# G824A.net
KiCad netlist of a schematic drawn in EAGLE
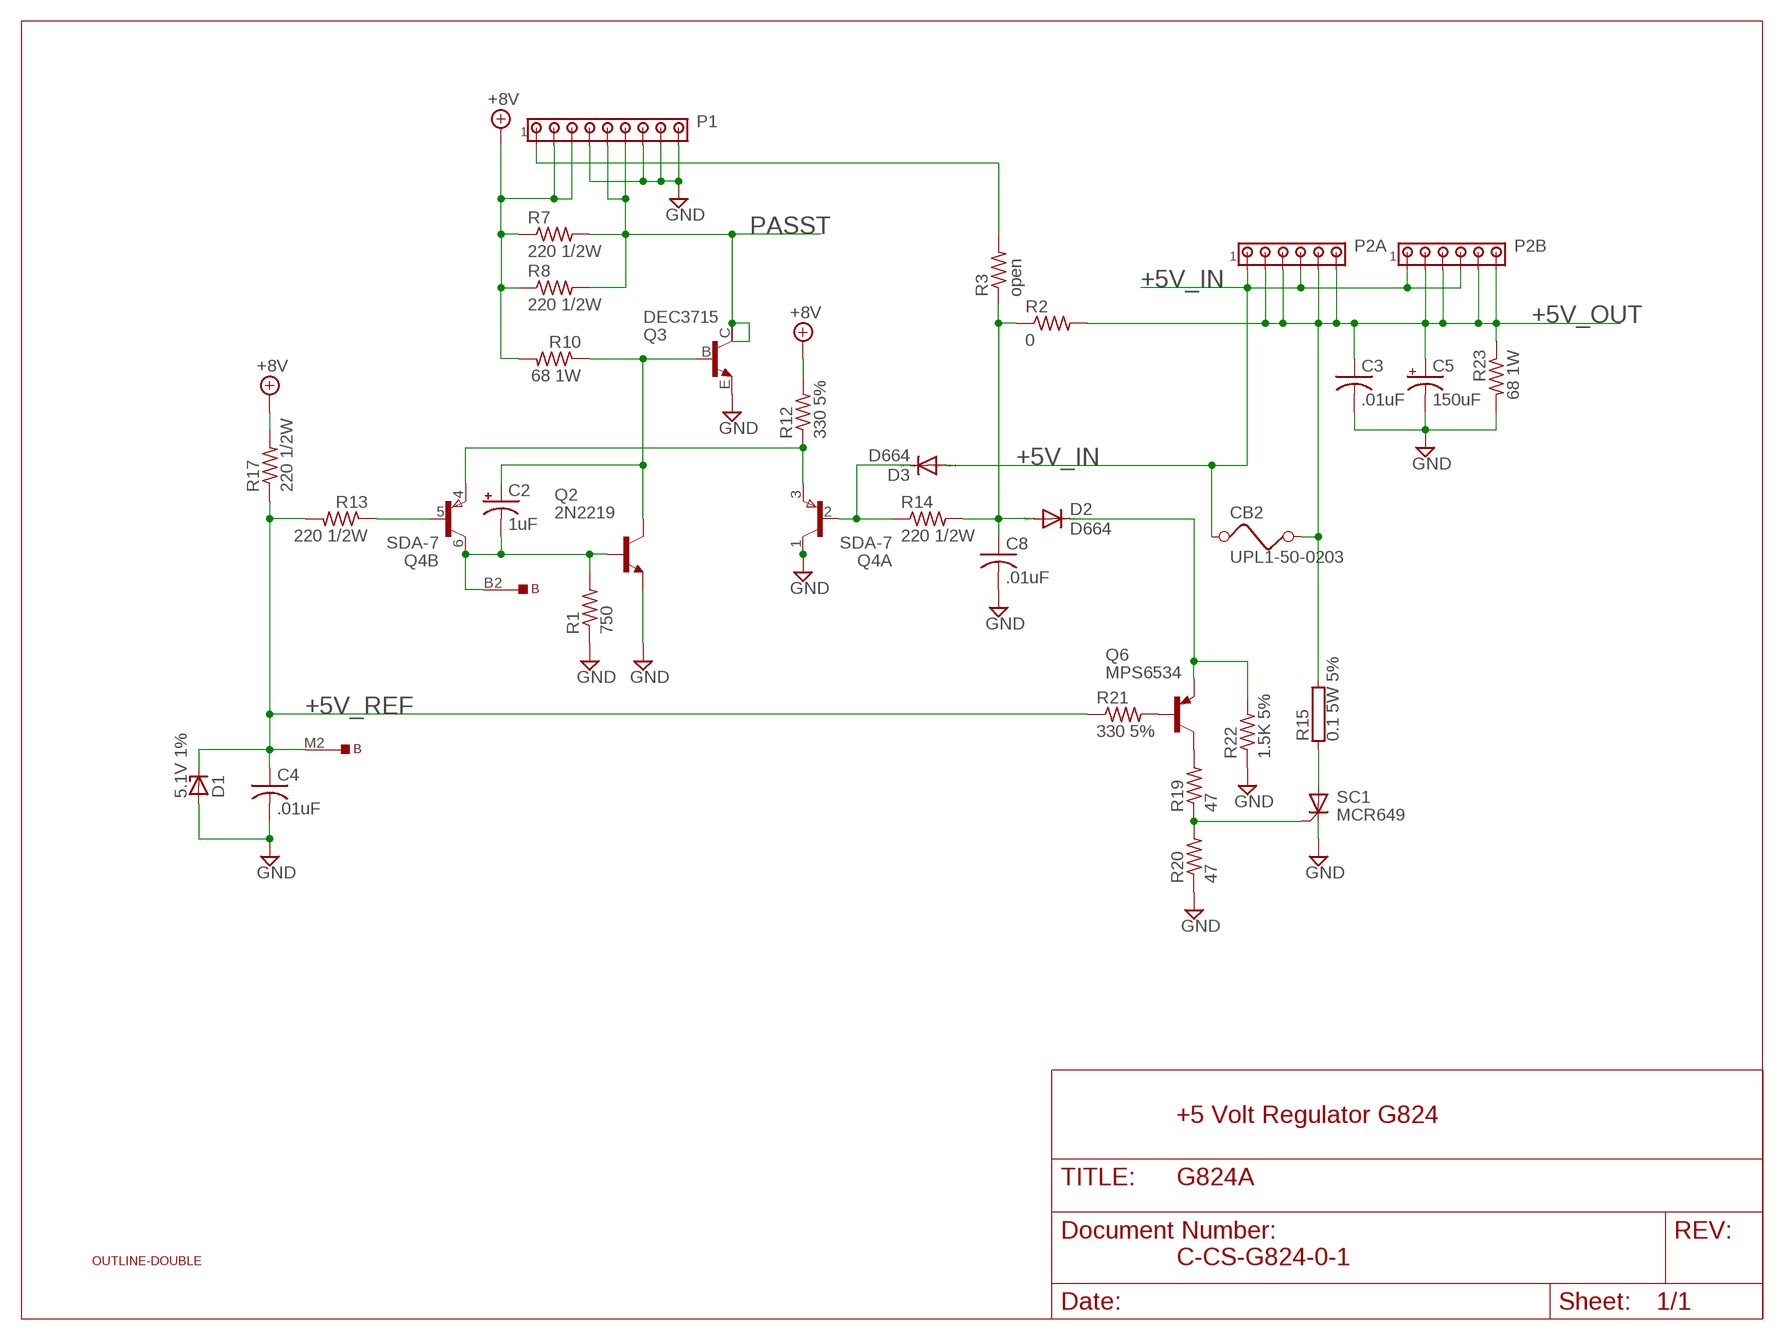
[diagram p0: schematic, sheet 1]

(export (version "E")
  (design (tool "Eeschema 10.0.6"))
  (components
    (comp (ref "B")
      (value "EDGE-TOP")
      (footprint "eagle-import:EDGE-CON2")
      (libsource (lib "eagle-import") (part "EDGE-TOP"))
    )
    (comp (ref "C2")
      (value "1uF")
      (footprint "eagle-import:E15-5")
      (libsource (lib "eagle-import") (part "CPOL-USE15-5AXIAL"))
    )
    (comp (ref "C3")
      (value ".01uF")
      (footprint "eagle-import:C063-025X075")
      (libsource (lib "eagle-import") (part "C-US"))
    )
    (comp (ref "C4")
      (value ".01uF")
      (footprint "eagle-import:C063-025X075")
      (libsource (lib "eagle-import") (part "C-US"))
    )
    (comp (ref "C5")
      (value "150uF")
      (footprint "eagle-import:E12-8")
      (libsource (lib "eagle-import") (part "CPOL-USE20-8AXIAL"))
    )
    (comp (ref "C8")
      (value ".01uF")
      (footprint "eagle-import:C063-025X075")
      (libsource (lib "eagle-import") (part "C-US"))
    )
    (comp (ref "CB2")
      (value "UPL1-50-0203")
      (footprint "eagle-import:UPL1-50")
      (libsource (lib "eagle-import") (part "UPL1-50"))
    )
    (comp (ref "D1")
      (value "5.1V 1%")
      (footprint "eagle-import:DO41Z10")
      (libsource (lib "eagle-import") (part "ZENER-DIODEDO41Z10"))
    )
    (comp (ref "D2")
      (value "D664")
      (footprint "eagle-import:DO35-10")
      (libsource (lib "eagle-import") (part "DIODE-DO35-10"))
    )
    (comp (ref "D3")
      (value "D664")
      (footprint "eagle-import:DO35-10")
      (libsource (lib "eagle-import") (part "DIODE-DO35-10"))
    )
    (comp (ref "P1")
      (value "350432-1")
      (footprint "eagle-import:350432-1")
      (libsource (lib "eagle-import") (part "350432-1"))
    )
    (comp (ref "P2A")
      (value "350431-1")
      (footprint "eagle-import:350431-1")
      (libsource (lib "eagle-import") (part "350431-1"))
    )
    (comp (ref "P2B")
      (value "350431-1")
      (footprint "eagle-import:350431-1")
      (libsource (lib "eagle-import") (part "350431-1"))
    )
    (comp (ref "Q2")
      (value "2N2219")
      (footprint "eagle-import:TO5")
      (libsource (lib "eagle-import") (part "2N2219"))
    )
    (comp (ref "Q3")
      (value "DEC3715")
      (footprint "eagle-import:TO3")
      (libsource (lib "eagle-import") (part "2N3772"))
    )
    (comp (ref "Q4")
      (value "SDA-7")
      (footprint "eagle-import:TO78")
      (libsource (lib "eagle-import") (part "MAT-03H"))
    )
    (comp (ref "Q6")
      (value "MPS6534")
      (footprint "eagle-import:TO5")
      (libsource (lib "eagle-import") (part "-PNP-TO5"))
    )
    (comp (ref "R1")
      (value "750")
      (footprint "eagle-import:0207_10")
      (libsource (lib "eagle-import") (part "R-US_0207/10"))
    )
    (comp (ref "R2")
      (value "0")
      (footprint "eagle-import:0207_10")
      (libsource (lib "eagle-import") (part "R-US_0207/10"))
    )
    (comp (ref "R3")
      (value "open")
      (footprint "eagle-import:0207_10")
      (libsource (lib "eagle-import") (part "R-US_0207/10"))
    )
    (comp (ref "R7")
      (value "220 1/2W")
      (footprint "eagle-import:0411_15")
      (libsource (lib "eagle-import") (part "R-US_0411/15"))
    )
    (comp (ref "R8")
      (value "220 1/2W")
      (footprint "eagle-import:0411_15")
      (libsource (lib "eagle-import") (part "R-US_0411/15"))
    )
    (comp (ref "R10")
      (value "68 1W")
      (footprint "eagle-import:0414_20")
      (libsource (lib "eagle-import") (part "R-US_0414/20"))
    )
    (comp (ref "R12")
      (value "330 5%")
      (footprint "eagle-import:0207_10")
      (libsource (lib "eagle-import") (part "R-US_0207/10"))
    )
    (comp (ref "R13")
      (value "220 1/2W")
      (footprint "eagle-import:0411_15")
      (libsource (lib "eagle-import") (part "R-US_0411/15"))
    )
    (comp (ref "R14")
      (value "220 1/2W")
      (footprint "eagle-import:0411_15")
      (libsource (lib "eagle-import") (part "R-US_0411/15"))
    )
    (comp (ref "R15")
      (value "0.1 5W 5%")
      (footprint "eagle-import:HPS932")
      (libsource (lib "eagle-import") (part "RHPS932"))
    )
    (comp (ref "R17")
      (value "220 1/2W")
      (footprint "eagle-import:0411_15")
      (libsource (lib "eagle-import") (part "R-US_0411/15"))
    )
    (comp (ref "R19")
      (value "47")
      (footprint "eagle-import:0207_10")
      (libsource (lib "eagle-import") (part "R-US_0207/10"))
    )
    (comp (ref "R20")
      (value "47")
      (footprint "eagle-import:0207_10")
      (libsource (lib "eagle-import") (part "R-US_0207/10"))
    )
    (comp (ref "R21")
      (value "330 5%")
      (footprint "eagle-import:0207_10")
      (libsource (lib "eagle-import") (part "R-US_0207/10"))
    )
    (comp (ref "R22")
      (value "1.5K 5%")
      (footprint "eagle-import:0207_10")
      (libsource (lib "eagle-import") (part "R-US_0207/10"))
    )
    (comp (ref "R23")
      (value "68 1W")
      (footprint "eagle-import:0414_20")
      (libsource (lib "eagle-import") (part "R-US_0414/20"))
    )
    (comp (ref "SC1")
      (value "MCR649")
      (footprint "eagle-import:TO3A")
      (libsource (lib "eagle-import") (part "MCR649"))
    )
    (comp (ref "U$1")
      (value "OUTLINE-DOUBLE")
      (footprint "eagle-import:DOUBLE")
      (libsource (lib "eagle-import") (part "OUTLINE-DOUBLE"))
    )
  )
  (nets
    (net (code "1") (name "+8V") (class "Default")
      (node (ref "P1") (pin "2") (pinfunction "2_2") (pintype "passive"))
      (node (ref "P1") (pin "3") (pinfunction "3_3") (pintype "passive"))
      (node (ref "R10") (pin "2") (pinfunction "2_2") (pintype "passive"))
      (node (ref "R12") (pin "2") (pinfunction "2_2") (pintype "passive"))
      (node (ref "R17") (pin "2") (pinfunction "2_2") (pintype "passive"))
      (node (ref "R7") (pin "1") (pinfunction "1_1") (pintype "passive"))
      (node (ref "R8") (pin "1") (pinfunction "1_1") (pintype "passive"))
    )
    (net (code "2") (name "/+5V_IN") (class "Default")
      (node (ref "CB2") (pin "1") (pinfunction "1_1") (pintype "passive"))
      (node (ref "D3") (pin "A") (pinfunction "A_A") (pintype "passive"))
      (node (ref "P2A") (pin "1") (pinfunction "1_1") (pintype "passive"))
      (node (ref "P2A") (pin "4") (pinfunction "4_4") (pintype "passive"))
      (node (ref "P2B") (pin "1") (pinfunction "1_1") (pintype "passive"))
      (node (ref "P2B") (pin "4") (pinfunction "4_4") (pintype "passive"))
    )
    (net (code "3") (name "/+5V_OUT") (class "Default")
      (node (ref "C3") (pin "1") (pinfunction "1_1") (pintype "passive"))
      (node (ref "C5") (pin "+") (pinfunction "+_+") (pintype "passive"))
      (node (ref "CB2") (pin "2") (pinfunction "2_2") (pintype "passive"))
      (node (ref "P2A") (pin "2") (pinfunction "2_2") (pintype "passive"))
      (node (ref "P2A") (pin "3") (pinfunction "3_3") (pintype "passive"))
      (node (ref "P2A") (pin "5") (pinfunction "5_5") (pintype "passive"))
      (node (ref "P2A") (pin "6") (pinfunction "6_6") (pintype "passive"))
      (node (ref "P2B") (pin "2") (pinfunction "2_2") (pintype "passive"))
      (node (ref "P2B") (pin "3") (pinfunction "3_3") (pintype "passive"))
      (node (ref "P2B") (pin "5") (pinfunction "5_5") (pintype "passive"))
      (node (ref "P2B") (pin "6") (pinfunction "6_6") (pintype "passive"))
      (node (ref "R15") (pin "2") (pinfunction "2_2") (pintype "passive"))
      (node (ref "R2") (pin "2") (pinfunction "2_2") (pintype "passive"))
      (node (ref "R23") (pin "1") (pinfunction "1_1") (pintype "passive"))
    )
    (net (code "4") (name "/+5V_REF") (class "Default")
      (node (ref "B") (pin "M2") (pinfunction "P_M2") (pintype "passive"))
      (node (ref "C4") (pin "1") (pinfunction "1_1") (pintype "passive"))
      (node (ref "D1") (pin "C") (pinfunction "C_C") (pintype "passive"))
      (node (ref "R13") (pin "2") (pinfunction "2_2") (pintype "passive"))
      (node (ref "R17") (pin "1") (pinfunction "1_1") (pintype "passive"))
      (node (ref "R21") (pin "1") (pinfunction "1_1") (pintype "passive"))
    )
    (net (code "5") (name "/PASST") (class "Default")
      (node (ref "P1") (pin "5") (pinfunction "5_5") (pintype "passive"))
      (node (ref "P1") (pin "6") (pinfunction "6_6") (pintype "passive"))
      (node (ref "Q3") (pin "C") (pinfunction "C_C") (pintype "passive"))
      (node (ref "Q3") (pin "C/") (pinfunction "C_C/") (pintype "passive"))
      (node (ref "R7") (pin "2") (pinfunction "2_2") (pintype "passive"))
      (node (ref "R8") (pin "2") (pinfunction "2_2") (pintype "passive"))
    )
    (net (code "6") (name "GND") (class "Default")
      (node (ref "C3") (pin "2") (pinfunction "2_2") (pintype "passive"))
      (node (ref "C4") (pin "2") (pinfunction "2_2") (pintype "passive"))
      (node (ref "C5") (pin "-") (pinfunction "-_-") (pintype "passive"))
      (node (ref "C8") (pin "2") (pinfunction "2_2") (pintype "passive"))
      (node (ref "D1") (pin "A") (pinfunction "A_A") (pintype "passive"))
      (node (ref "P1") (pin "4") (pinfunction "4_4") (pintype "passive"))
      (node (ref "P1") (pin "7") (pinfunction "7_7") (pintype "passive"))
      (node (ref "P1") (pin "8") (pinfunction "8_8") (pintype "passive"))
      (node (ref "P1") (pin "9") (pinfunction "9_9") (pintype "passive"))
      (node (ref "Q2") (pin "1") (pinfunction "E_1") (pintype "passive"))
      (node (ref "Q3") (pin "E") (pinfunction "E_E") (pintype "passive"))
      (node (ref "Q4") (pin "1") (pinfunction "C_1") (pintype "passive"))
      (node (ref "R1") (pin "1") (pinfunction "1_1") (pintype "passive"))
      (node (ref "R20") (pin "1") (pinfunction "1_1") (pintype "passive"))
      (node (ref "R22") (pin "1") (pinfunction "1_1") (pintype "passive"))
      (node (ref "R23") (pin "2") (pinfunction "2_2") (pintype "passive"))
      (node (ref "SC1") (pin "1") (pinfunction "C_1") (pintype "passive"))
    )
    (net (code "7") (name "Net-(BD-P)") (class "Default")
      (node (ref "B") (pin "B2") (pinfunction "P_B2") (pintype "passive"))
      (node (ref "C2") (pin "-") (pinfunction "-_-") (pintype "passive"))
      (node (ref "Q2") (pin "2") (pinfunction "B_2") (pintype "passive"))
      (node (ref "Q4") (pin "6") (pinfunction "C_6") (pintype "passive"))
      (node (ref "R1") (pin "2") (pinfunction "2_2") (pintype "passive"))
    )
    (net (code "8") (name "Net-(C8-Pad1)") (class "Default")
      (node (ref "C8") (pin "1") (pinfunction "1_1") (pintype "passive"))
      (node (ref "D2") (pin "A") (pinfunction "A_A") (pintype "passive"))
      (node (ref "R14") (pin "2") (pinfunction "2_2") (pintype "passive"))
      (node (ref "R2") (pin "1") (pinfunction "1_1") (pintype "passive"))
      (node (ref "R3") (pin "1") (pinfunction "1_1") (pintype "passive"))
    )
    (net (code "9") (name "Net-(P1-Pad1)") (class "Default")
      (node (ref "P1") (pin "1") (pinfunction "1_1") (pintype "passive"))
      (node (ref "R3") (pin "2") (pinfunction "2_2") (pintype "passive"))
    )
    (net (code "10") (name "Net-(Q2-C)") (class "Default")
      (node (ref "C2") (pin "+") (pinfunction "+_+") (pintype "passive"))
      (node (ref "Q2") (pin "3") (pinfunction "C_3") (pintype "passive"))
      (node (ref "Q3") (pin "B") (pinfunction "B_B") (pintype "passive"))
      (node (ref "R10") (pin "1") (pinfunction "1_1") (pintype "passive"))
    )
    (net (code "11") (name "Net-(Q4A-B)") (class "Default")
      (node (ref "D3") (pin "C") (pinfunction "C_C") (pintype "passive"))
      (node (ref "Q4") (pin "2") (pinfunction "B_2") (pintype "passive"))
      (node (ref "R14") (pin "1") (pinfunction "1_1") (pintype "passive"))
    )
    (net (code "12") (name "Net-(Q4A-E)") (class "Default")
      (node (ref "Q4") (pin "3") (pinfunction "E_3") (pintype "passive"))
      (node (ref "Q4") (pin "4") (pinfunction "E_4") (pintype "passive"))
      (node (ref "R12") (pin "1") (pinfunction "1_1") (pintype "passive"))
    )
    (net (code "13") (name "Net-(Q4B-B)") (class "Default")
      (node (ref "Q4") (pin "5") (pinfunction "B_5") (pintype "passive"))
      (node (ref "R13") (pin "1") (pinfunction "1_1") (pintype "passive"))
    )
    (net (code "14") (name "Net-(Q6-B)") (class "Default")
      (node (ref "Q6") (pin "2") (pinfunction "B_2") (pintype "passive"))
      (node (ref "R21") (pin "2") (pinfunction "2_2") (pintype "passive"))
    )
    (net (code "15") (name "Net-(Q6-C)") (class "Default")
      (node (ref "Q6") (pin "3") (pinfunction "C_3") (pintype "passive"))
      (node (ref "R19") (pin "2") (pinfunction "2_2") (pintype "passive"))
    )
    (net (code "16") (name "Net-(Q6-E)") (class "Default")
      (node (ref "D2") (pin "C") (pinfunction "C_C") (pintype "passive"))
      (node (ref "Q6") (pin "1") (pinfunction "E_1") (pintype "passive"))
      (node (ref "R22") (pin "2") (pinfunction "2_2") (pintype "passive"))
    )
    (net (code "17") (name "Net-(SC1-A)") (class "Default")
      (node (ref "R15") (pin "1") (pinfunction "1_1") (pintype "passive"))
      (node (ref "SC1") (pin "3") (pinfunction "A_3") (pintype "passive"))
    )
    (net (code "18") (name "Net-(SC1-G)") (class "Default")
      (node (ref "R19") (pin "1") (pinfunction "1_1") (pintype "passive"))
      (node (ref "R20") (pin "2") (pinfunction "2_2") (pintype "passive"))
      (node (ref "SC1") (pin "2") (pinfunction "G_2") (pintype "passive"))
    )
  )
)
